# BUCK.net
KiCad netlist of a schematic drawn in Altium Designer
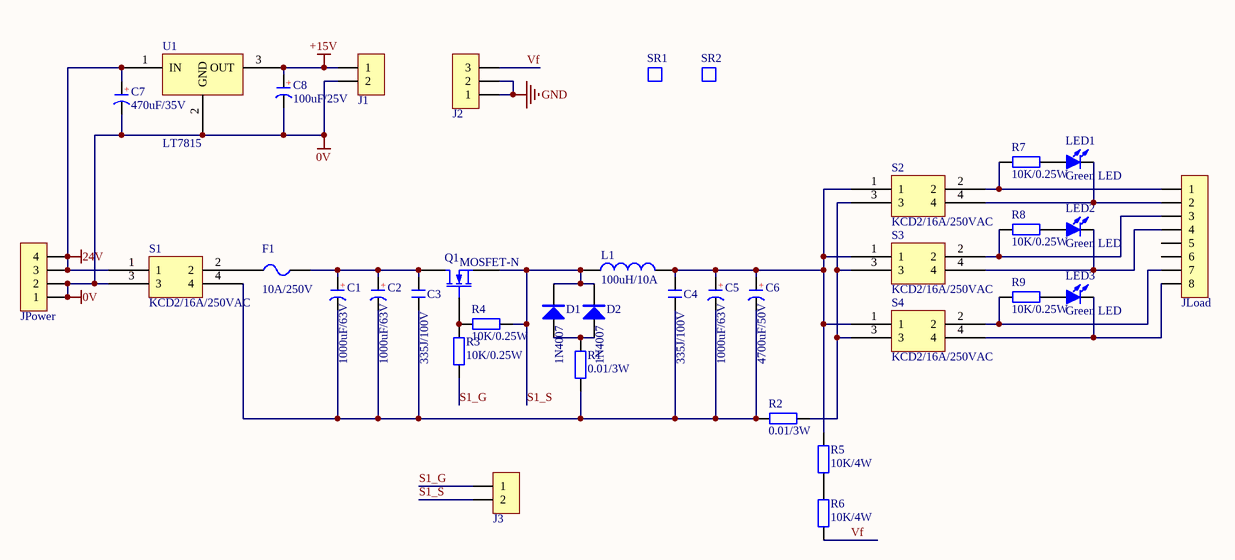
[diagram p0: BUCK.SchDoc]

(export (version "E")
  (design (tool "Eeschema 10.0.6"))
  (components
    (comp (ref "C1")
      (value "1000uF/63V")
      (footprint "CAP 1.5*4*8")
      (description "直插电解电容")
      (fields (field (name "版权归属") "源创客"))
      (libsource (lib "电阻-电容-电感") (part "C-CAP"))
    )
    (comp (ref "C2")
      (value "1000uF/63V")
      (footprint "CAP 1.5*4*8")
      (description "直插电解电容")
      (fields (field (name "版权归属") "源创客"))
      (libsource (lib "电阻-电容-电感") (part "C-CAP"))
    )
    (comp (ref "C3")
      (value "335J/100V")
      (footprint "C 0805")
      (description "无极性贴片电容")
      (fields (field (name "版权归属") "源创客"))
      (libsource (lib "电阻-电容-电感") (part "C"))
    )
    (comp (ref "C4")
      (value "335J/100V")
      (footprint "C 0805")
      (description "无极性贴片电容")
      (fields (field (name "版权归属") "源创客"))
      (libsource (lib "电阻-电容-电感") (part "C"))
    )
    (comp (ref "C5")
      (value "1000uF/63V")
      (footprint "CAP 1.5*4*8")
      (description "直插电解电容")
      (fields (field (name "版权归属") "源创客"))
      (libsource (lib "电阻-电容-电感") (part "C-CAP"))
    )
    (comp (ref "C6")
      (value "4700uF/50V")
      (footprint "CAP 1.5*4*8")
      (description "直插电解电容")
      (fields (field (name "版权归属") "源创客"))
      (libsource (lib "电阻-电容-电感") (part "C-CAP"))
    )
    (comp (ref "C7")
      (value "470uF/35V")
      (footprint "CAP 1.5*4*8")
      (description "直插电解电容")
      (fields (field (name "版权归属") "源创客"))
      (libsource (lib "电阻-电容-电感") (part "C-CAP"))
    )
    (comp (ref "C8")
      (value "100uF/25V")
      (footprint "CAP 1.5*4*8")
      (description "直插电解电容")
      (fields (field (name "版权归属") "源创客"))
      (libsource (lib "电阻-电容-电感") (part "C-CAP"))
    )
    (comp (ref "D1")
      (value "1N4007")
      (footprint "DO-41")
      (description "整流二极管")
      (fields (field (name "版权归属") "源创客"))
      (libsource (lib "二极管-整流桥") (part "1N4007"))
    )
    (comp (ref "D2")
      (value "1N4007")
      (footprint "DO-41")
      (description "整流二极管")
      (fields (field (name "版权归属") "源创客"))
      (libsource (lib "二极管-整流桥") (part "1N4007"))
    )
    (comp (ref "F1")
      (value "10A/250V")
      (footprint "FU 5x20")
      (description "5*20保险丝")
      (fields (field (name "版权归属") "源创客"))
      (libsource (lib "保险丝-晶振") (part "FU 5x20"))
    )
    (comp (ref "J1")
      (value "HDR-1X2")
      (footprint "PH2.0 D-L-2P")
      (description "2P接插件")
      (fields (field (name "版权归属") "源创客"))
      (libsource (lib "接插件") (part "Header 2"))
    )
    (comp (ref "J2")
      (value "HDR-1X3")
      (footprint "PH2.0 D-L-3P")
      (description "3P接插件")
      (fields (field (name "版权归属") "源创客"))
      (libsource (lib "接插件") (part "Header 3"))
    )
    (comp (ref "J3")
      (value "HDR-1X2")
      (footprint "PH2.0 D-L-2P")
      (description "2P接插件")
      (fields (field (name "版权归属") "源创客"))
      (libsource (lib "接插件") (part "Header 2"))
    )
    (comp (ref "JLoad")
      (value "HDR-1X8")
      (footprint "KF2EDGK5.08-8P")
      (description "8P接插件")
      (fields (field (name "版权归属") "源创客"))
      (libsource (lib "接插件") (part "Header 8"))
    )
    (comp (ref "JPower")
      (value "HDR-1X4")
      (footprint "PH2.0 D-L-4P")
      (description "4P接插件")
      (fields (field (name "版权归属") "源创客"))
      (libsource (lib "接插件") (part "Header 4"))
    )
    (comp (ref "L1")
      (value "100uH/10A")
      (footprint "L 0805")
      (description "小功率贴片电感")
      (fields (field (name "版权归属") "源创客"))
      (libsource (lib "电阻-电容-电感") (part "L"))
    )
    (comp (ref "LED1")
      (value "Green LED")
      (footprint "LED 0805G")
      (description "贴片LED")
      (fields (field (name "版权归属") "源创客"))
      (libsource (lib "LED") (part "LED-SMD"))
    )
    (comp (ref "LED2")
      (value "Green LED")
      (footprint "LED 0805G")
      (description "贴片LED")
      (fields (field (name "版权归属") "源创客"))
      (libsource (lib "LED") (part "LED-SMD"))
    )
    (comp (ref "LED3")
      (value "Green LED")
      (footprint "LED 0805G")
      (description "贴片LED")
      (fields (field (name "版权归属") "源创客"))
      (libsource (lib "LED") (part "LED-SMD"))
    )
    (comp (ref "Q1")
      (value "MOSFET-N")
      (footprint "TO:TO220A")
      (description "N-Channel MOSFET")
      (fields (field (name "PUBLISHER") "Altium Limited"))
      (libsource (lib "Miscellaneous Devices") (part "MOSFET-N"))
    )
    (comp (ref "R1")
      (value "0.01/3W")
      (footprint "R 0805")
      (description "贴片电阻")
      (fields (field (name "版权归属") "源创客"))
      (libsource (lib "电阻-电容-电感") (part "R"))
    )
    (comp (ref "R2")
      (value "0.01/3W")
      (footprint "R 0805")
      (description "贴片电阻")
      (fields (field (name "版权归属") "源创客"))
      (libsource (lib "电阻-电容-电感") (part "R"))
    )
    (comp (ref "R3")
      (value "10K/0.25W")
      (footprint "R 0805")
      (description "贴片电阻")
      (fields (field (name "版权归属") "源创客"))
      (libsource (lib "电阻-电容-电感") (part "R"))
    )
    (comp (ref "R4")
      (value "10K/0.25W")
      (footprint "R 0805")
      (description "贴片电阻")
      (fields (field (name "版权归属") "源创客"))
      (libsource (lib "电阻-电容-电感") (part "R"))
    )
    (comp (ref "R5")
      (value "10K/4W")
      (footprint "R 0805")
      (description "贴片电阻")
      (fields (field (name "版权归属") "源创客"))
      (libsource (lib "电阻-电容-电感") (part "R"))
    )
    (comp (ref "R6")
      (value "10K/4W")
      (footprint "R 0805")
      (description "贴片电阻")
      (fields (field (name "版权归属") "源创客"))
      (libsource (lib "电阻-电容-电感") (part "R"))
    )
    (comp (ref "R7")
      (value "10K/0.25W")
      (footprint "R 0805")
      (description "贴片电阻")
      (fields (field (name "版权归属") "源创客"))
      (libsource (lib "电阻-电容-电感") (part "R"))
    )
    (comp (ref "R8")
      (value "10K/0.25W")
      (footprint "R 0805")
      (description "贴片电阻")
      (fields (field (name "版权归属") "源创客"))
      (libsource (lib "电阻-电容-电感") (part "R"))
    )
    (comp (ref "R9")
      (value "10K/0.25W")
      (footprint "R 0805")
      (description "贴片电阻")
      (fields (field (name "版权归属") "源创客"))
      (libsource (lib "电阻-电容-电感") (part "R"))
    )
    (comp (ref "S1")
      (value "KCD2/16A/250VAC")
      (footprint "开关:KCD1-104-W")
      (libsource (lib "KCD2") (part "KCD2/16A/250VAC"))
    )
    (comp (ref "S2")
      (value "KCD2/16A/250VAC")
      (footprint "开关:KCD1-104-W")
      (libsource (lib "KCD2") (part "KCD2/16A/250VAC"))
    )
    (comp (ref "S3")
      (value "KCD2/16A/250VAC")
      (footprint "开关:KCD1-104-W")
      (libsource (lib "KCD2") (part "KCD2/16A/250VAC"))
    )
    (comp (ref "S4")
      (value "KCD2/16A/250VAC")
      (footprint "开关:KCD1-104-W")
      (libsource (lib "KCD2") (part "KCD2/16A/250VAC"))
    )
    (comp (ref "SR1")
      (value "散热片")
      (footprint "散热片")
      (fields (field (name "版权归属") "源创客"))
      (libsource (lib "未分类器件") (part "S1"))
    )
    (comp (ref "SR2")
      (value "散热片")
      (footprint "散热片")
      (fields (field (name "版权归属") "源创客"))
      (libsource (lib "未分类器件") (part "S1"))
    )
    (comp (ref "U1") (value "LT7815") (footprint "TO:TO220A") (libsource (lib "LT7815") (part "LT7815")))
  )
  (nets
    (net (code "1") (name "+15V") (class "Default")
      (node (ref "C8") (pin "1") (pinfunction "A_1") (pintype "passive"))
      (node (ref "J1") (pin "1") (pinfunction "1_1") (pintype "passive"))
      (node (ref "U1") (pin "3") (pinfunction "OUT_3") (pintype "passive"))
    )
    (net (code "2") (name "/S1_G") (class "Default")
      (node (ref "J3") (pin "1") (pinfunction "1_1") (pintype "passive"))
      (node (ref "R3") (pin "2") (pinfunction "2_2") (pintype "passive"))
    )
    (net (code "3") (name "/S1_S") (class "Default")
      (node (ref "D1") (pin "2") (pinfunction "K_2") (pintype "passive"))
      (node (ref "D2") (pin "2") (pinfunction "K_2") (pintype "passive"))
      (node (ref "J3") (pin "2") (pinfunction "2_2") (pintype "passive"))
      (node (ref "L1") (pin "1") (pinfunction "1_1") (pintype "passive"))
      (node (ref "Q1") (pin "3") (pinfunction "S_3") (pintype "passive"))
      (node (ref "R4") (pin "2") (pinfunction "2_2") (pintype "passive"))
    )
    (net (code "4") (name "/Vf") (class "Default")
      (node (ref "J2") (pin "3") (pinfunction "3_3") (pintype "passive"))
      (node (ref "R6") (pin "1") (pinfunction "1_1") (pintype "passive"))
    )
    (net (code "5") (name "0V") (class "Default")
      (node (ref "C7") (pin "2") (pinfunction "K_2") (pintype "passive"))
      (node (ref "C8") (pin "2") (pinfunction "K_2") (pintype "passive"))
      (node (ref "J1") (pin "2") (pinfunction "2_2") (pintype "passive"))
      (node (ref "JPower") (pin "1") (pinfunction "1_1") (pintype "passive"))
      (node (ref "JPower") (pin "2") (pinfunction "2_2") (pintype "passive"))
      (node (ref "S1") (pin "3") (pinfunction "3_3") (pintype "passive"))
      (node (ref "U1") (pin "2") (pinfunction "GND_2") (pintype "passive"))
    )
    (net (code "6") (name "24V") (class "Default")
      (node (ref "C7") (pin "1") (pinfunction "A_1") (pintype "passive"))
      (node (ref "JPower") (pin "3") (pinfunction "3_3") (pintype "passive"))
      (node (ref "JPower") (pin "4") (pinfunction "4_4") (pintype "passive"))
      (node (ref "S1") (pin "1") (pinfunction "1_1") (pintype "passive"))
      (node (ref "U1") (pin "1") (pinfunction "IN_1") (pintype "passive"))
    )
    (net (code "7") (name "GND") (class "Default")
      (node (ref "J2") (pin "1") (pinfunction "1_1") (pintype "passive"))
      (node (ref "J2") (pin "2") (pinfunction "2_2") (pintype "passive"))
    )
    (net (code "8") (name "Net-(C1-A)") (class "Default")
      (node (ref "C1") (pin "1") (pinfunction "A_1") (pintype "passive"))
      (node (ref "C2") (pin "1") (pinfunction "A_1") (pintype "passive"))
      (node (ref "C3") (pin "1") (pinfunction "1_1") (pintype "passive"))
      (node (ref "F1") (pin "1") (pinfunction "1_1") (pintype "passive"))
      (node (ref "Q1") (pin "1") (pinfunction "D_1") (pintype "passive"))
    )
    (net (code "9") (name "Net-(C1-K)") (class "Default")
      (node (ref "C1") (pin "2") (pinfunction "K_2") (pintype "passive"))
      (node (ref "C2") (pin "2") (pinfunction "K_2") (pintype "passive"))
      (node (ref "C3") (pin "2") (pinfunction "2_2") (pintype "passive"))
      (node (ref "C4") (pin "2") (pinfunction "2_2") (pintype "passive"))
      (node (ref "C5") (pin "2") (pinfunction "K_2") (pintype "passive"))
      (node (ref "C6") (pin "2") (pinfunction "K_2") (pintype "passive"))
      (node (ref "R1") (pin "1") (pinfunction "1_1") (pintype "passive"))
      (node (ref "R2") (pin "2") (pinfunction "2_2") (pintype "passive"))
      (node (ref "S1") (pin "4") (pinfunction "4_4") (pintype "passive"))
    )
    (net (code "10") (name "Net-(C5-A)") (class "Default")
      (node (ref "C4") (pin "1") (pinfunction "1_1") (pintype "passive"))
      (node (ref "C5") (pin "1") (pinfunction "A_1") (pintype "passive"))
      (node (ref "C6") (pin "1") (pinfunction "A_1") (pintype "passive"))
      (node (ref "L1") (pin "2") (pinfunction "2_2") (pintype "passive"))
      (node (ref "R5") (pin "2") (pinfunction "2_2") (pintype "passive"))
      (node (ref "S2") (pin "1") (pinfunction "1_1") (pintype "passive"))
      (node (ref "S3") (pin "1") (pinfunction "1_1") (pintype "passive"))
      (node (ref "S4") (pin "1") (pinfunction "1_1") (pintype "passive"))
    )
    (net (code "11") (name "Net-(D1-A)") (class "Default")
      (node (ref "D1") (pin "1") (pinfunction "A_1") (pintype "passive"))
      (node (ref "D2") (pin "1") (pinfunction "A_1") (pintype "passive"))
      (node (ref "R1") (pin "2") (pinfunction "2_2") (pintype "passive"))
    )
    (net (code "12") (name "Net-(F1-Pad2)") (class "Default")
      (node (ref "F1") (pin "2") (pinfunction "2_2") (pintype "passive"))
      (node (ref "S1") (pin "2") (pinfunction "2_2") (pintype "passive"))
    )
    (net (code "13") (name "Net-(JLoad-Pad1)") (class "Default")
      (node (ref "JLoad") (pin "1") (pinfunction "1_1") (pintype "passive"))
      (node (ref "R7") (pin "2") (pinfunction "2_2") (pintype "passive"))
      (node (ref "S2") (pin "2") (pinfunction "2_2") (pintype "passive"))
    )
    (net (code "14") (name "Net-(JLoad-Pad3)") (class "Default")
      (node (ref "JLoad") (pin "3") (pinfunction "3_3") (pintype "passive"))
      (node (ref "R8") (pin "2") (pinfunction "2_2") (pintype "passive"))
      (node (ref "S3") (pin "2") (pinfunction "2_2") (pintype "passive"))
    )
    (net (code "15") (name "Net-(JLoad-Pad7)") (class "Default")
      (node (ref "JLoad") (pin "7") (pinfunction "7_7") (pintype "passive"))
      (node (ref "R9") (pin "2") (pinfunction "2_2") (pintype "passive"))
      (node (ref "S4") (pin "2") (pinfunction "2_2") (pintype "passive"))
    )
    (net (code "16") (name "Net-(LED1-A)") (class "Default")
      (node (ref "LED1") (pin "1") (pinfunction "A_1") (pintype "passive"))
      (node (ref "R7") (pin "1") (pinfunction "1_1") (pintype "passive"))
    )
    (net (code "17") (name "Net-(LED1-K)") (class "Default")
      (node (ref "JLoad") (pin "2") (pinfunction "2_2") (pintype "passive"))
      (node (ref "LED1") (pin "2") (pinfunction "K_2") (pintype "passive"))
      (node (ref "S2") (pin "4") (pinfunction "4_4") (pintype "passive"))
    )
    (net (code "18") (name "Net-(LED2-A)") (class "Default")
      (node (ref "LED2") (pin "1") (pinfunction "A_1") (pintype "passive"))
      (node (ref "R8") (pin "1") (pinfunction "1_1") (pintype "passive"))
    )
    (net (code "19") (name "Net-(LED2-K)") (class "Default")
      (node (ref "JLoad") (pin "4") (pinfunction "4_4") (pintype "passive"))
      (node (ref "LED2") (pin "2") (pinfunction "K_2") (pintype "passive"))
      (node (ref "S3") (pin "4") (pinfunction "4_4") (pintype "passive"))
    )
    (net (code "20") (name "Net-(LED3-A)") (class "Default")
      (node (ref "LED3") (pin "1") (pinfunction "A_1") (pintype "passive"))
      (node (ref "R9") (pin "1") (pinfunction "1_1") (pintype "passive"))
    )
    (net (code "21") (name "Net-(LED3-K)") (class "Default")
      (node (ref "JLoad") (pin "8") (pinfunction "8_8") (pintype "passive"))
      (node (ref "LED3") (pin "2") (pinfunction "K_2") (pintype "passive"))
      (node (ref "S4") (pin "4") (pinfunction "4_4") (pintype "passive"))
    )
    (net (code "22") (name "Net-(Q1-G)") (class "Default")
      (node (ref "Q1") (pin "2") (pinfunction "G_2") (pintype "passive"))
      (node (ref "R3") (pin "1") (pinfunction "1_1") (pintype "passive"))
      (node (ref "R4") (pin "1") (pinfunction "1_1") (pintype "passive"))
    )
    (net (code "23") (name "Net-(R2-Pad1)") (class "Default")
      (node (ref "R2") (pin "1") (pinfunction "1_1") (pintype "passive"))
      (node (ref "S2") (pin "3") (pinfunction "3_3") (pintype "passive"))
      (node (ref "S3") (pin "3") (pinfunction "3_3") (pintype "passive"))
      (node (ref "S4") (pin "3") (pinfunction "3_3") (pintype "passive"))
    )
    (net (code "24") (name "Net-(R5-Pad1)") (class "Default")
      (node (ref "R5") (pin "1") (pinfunction "1_1") (pintype "passive"))
      (node (ref "R6") (pin "2") (pinfunction "2_2") (pintype "passive"))
    )
    (net (code "25") (name "unconnected-(JLoad-Pad5)") (class "Default")
      (node (ref "JLoad") (pin "5") (pinfunction "5_5") (pintype "passive"))
    )
    (net (code "26") (name "unconnected-(JLoad-Pad6)") (class "Default")
      (node (ref "JLoad") (pin "6") (pinfunction "6_6") (pintype "passive"))
    )
  )
)
